# Adapter_board.net
KiCad netlist of a schematic drawn in EAGLE
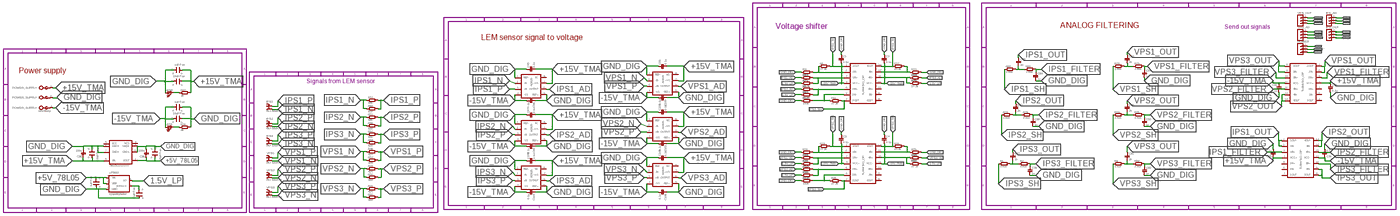
[diagram p0: schematic, sheet 1, overview]
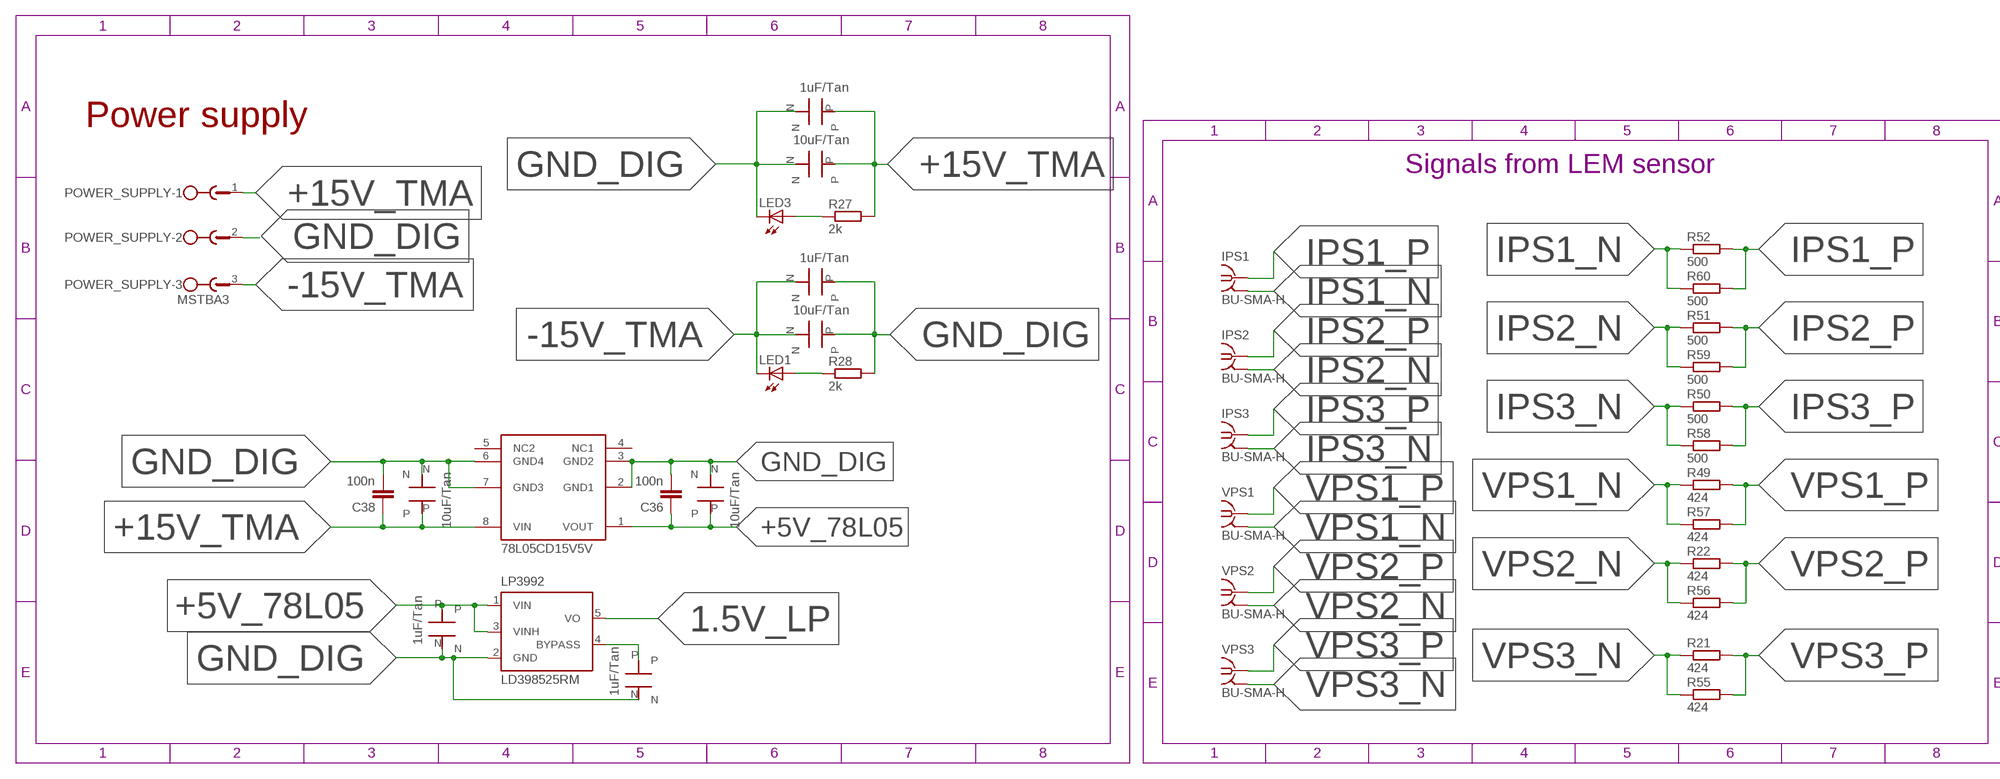
[diagram p1: schematic, sheet 1, part 1 of 4]
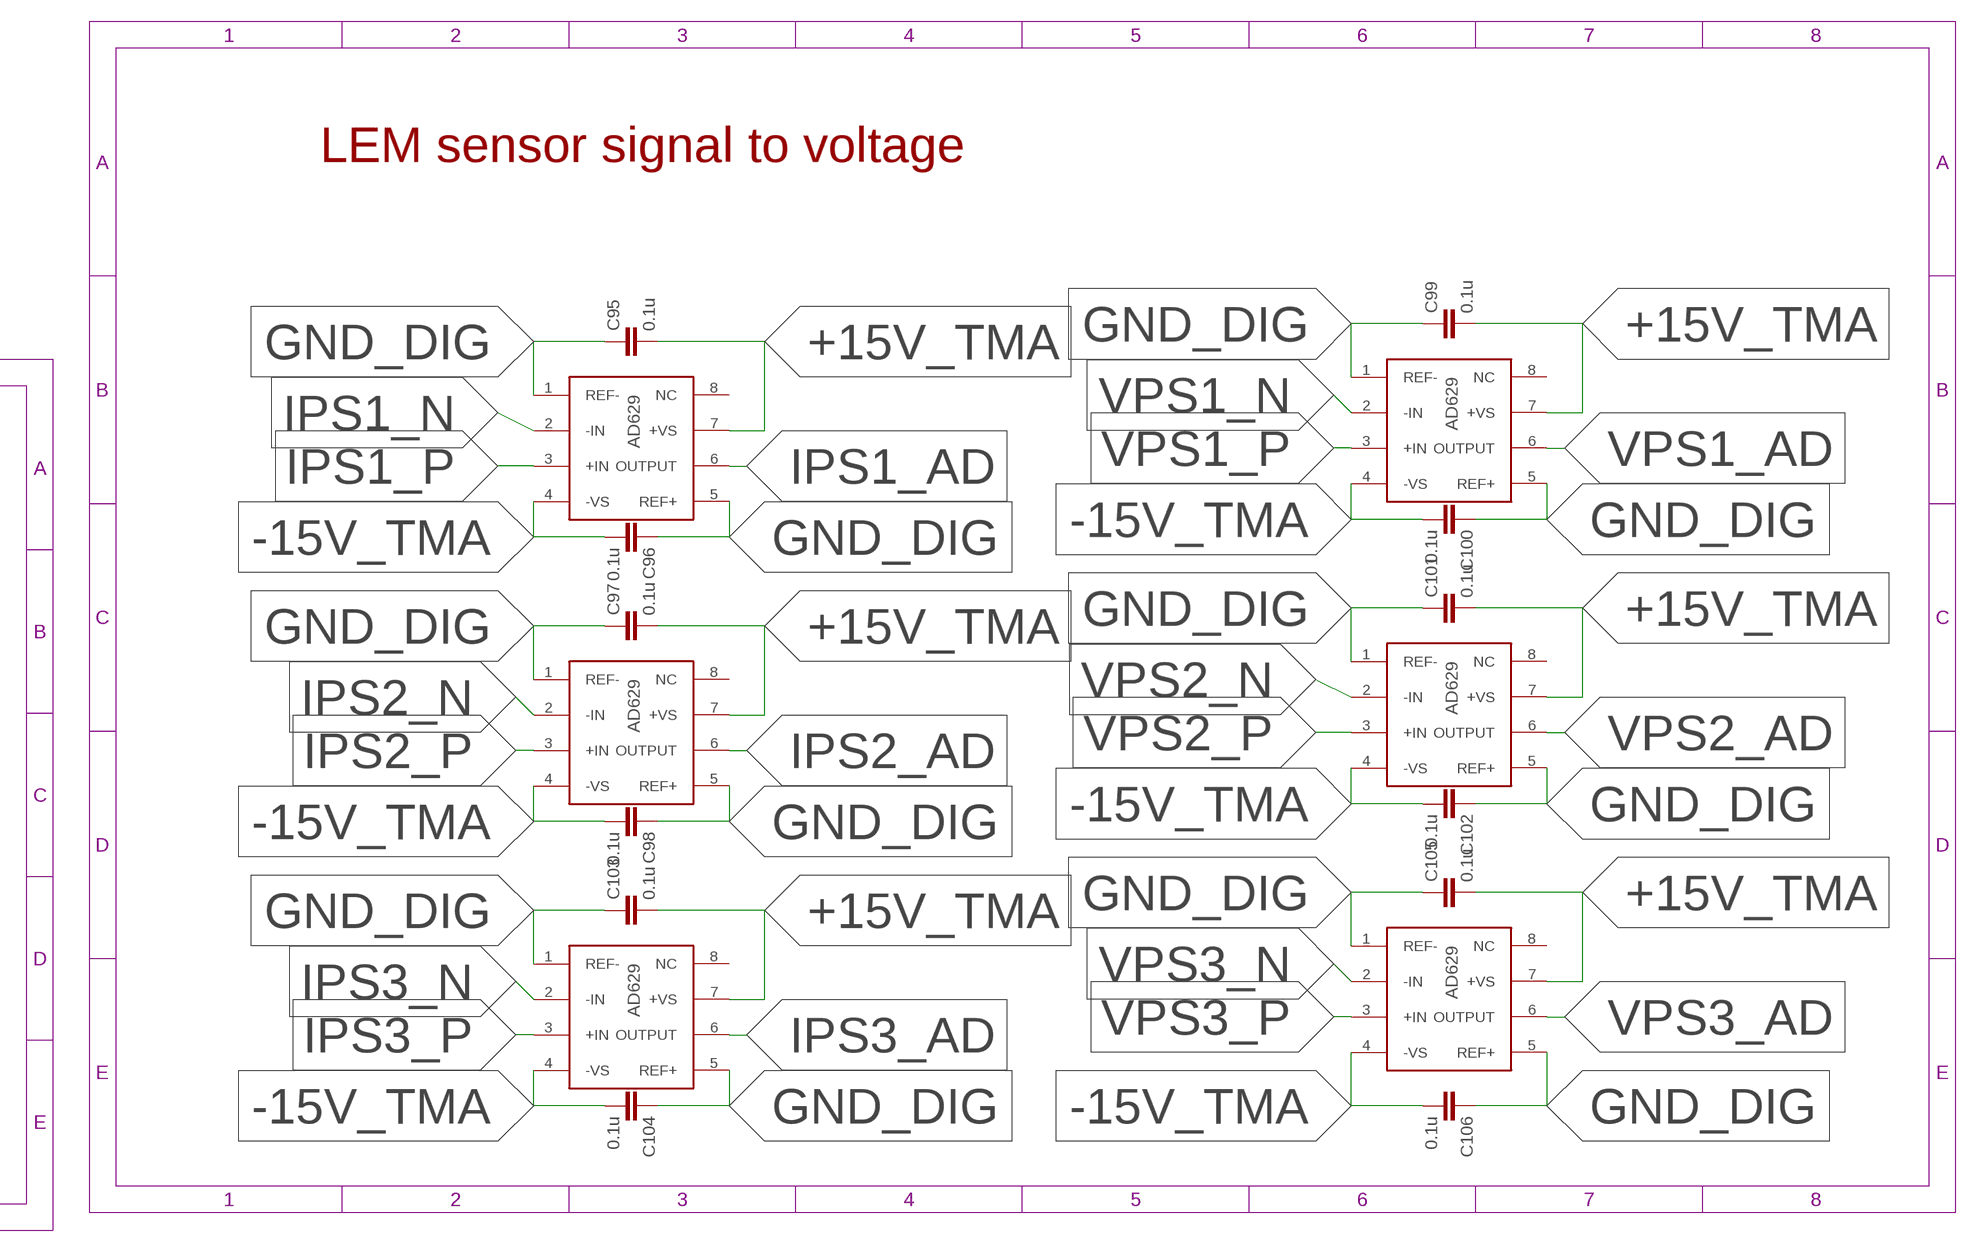
[diagram p2: schematic, sheet 1, part 2 of 4]
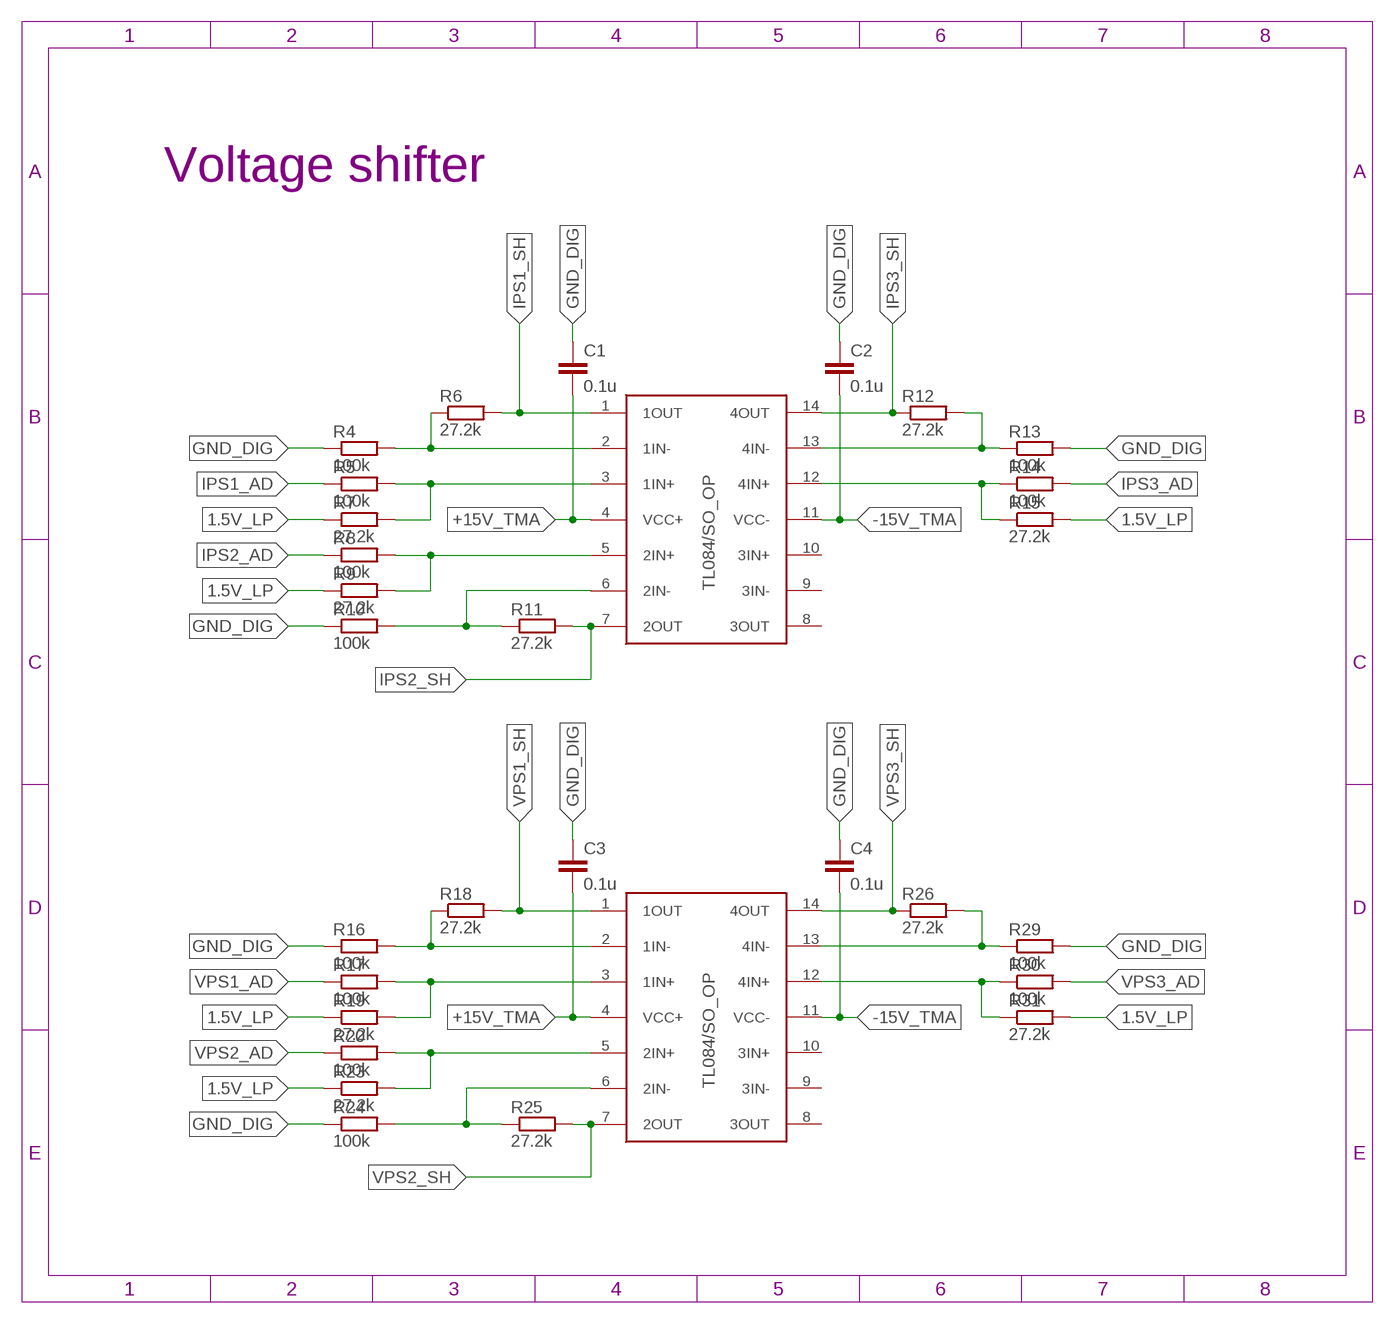
[diagram p3: schematic, sheet 1, part 3 of 4]
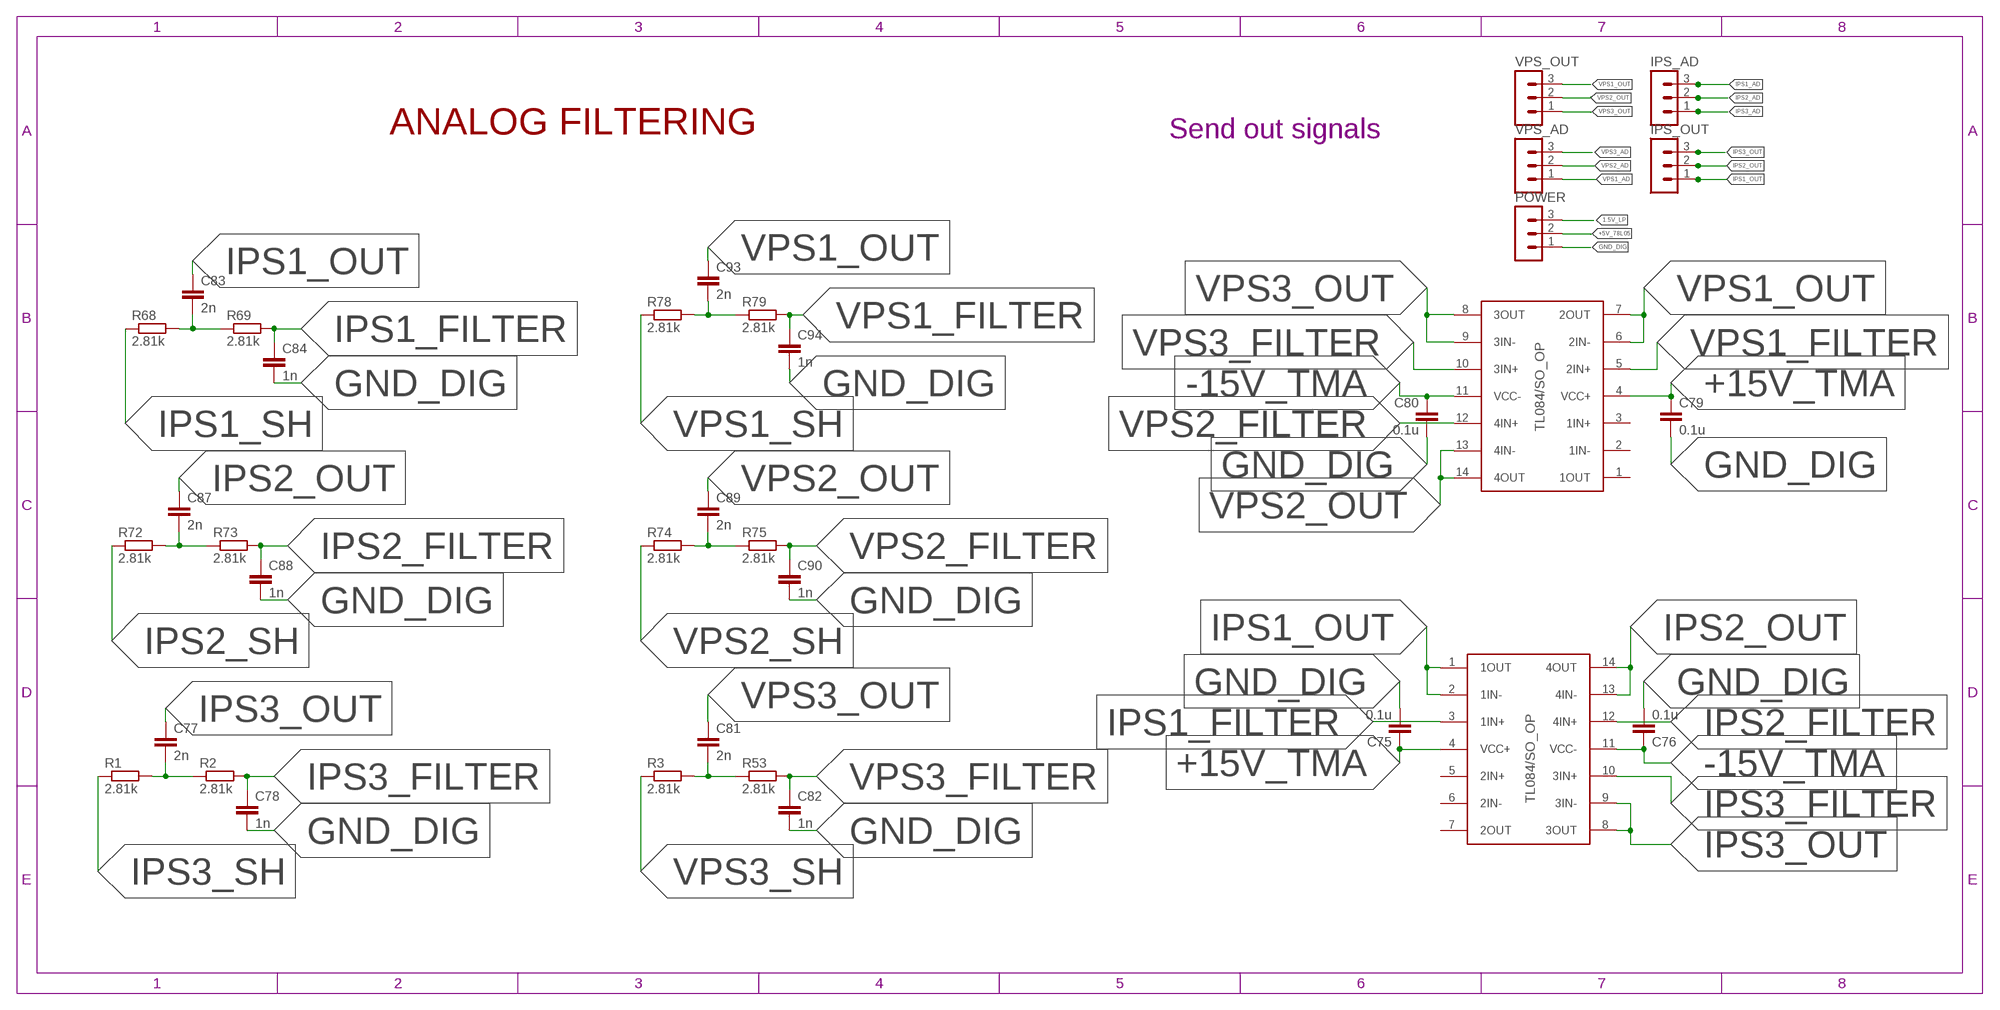
[diagram p4: schematic, sheet 1, part 4 of 4]

(export (version "E")
  (design (tool "Eeschema 10.0.6"))
  (components
    (comp (ref "78L05")
      (value "78L05CD15V5VONLINE")
      (footprint "eagle-import:78L05CD15V5V_LIB")
      (libsource (lib "eagle-import") (part "78L05CD15V5VONLINE"))
    )
    (comp (ref "C1")
      (value "0.1u")
      (footprint "eagle-import:C0805")
      (libsource (lib "eagle-import") (part "C-EUC0805"))
    )
    (comp (ref "C2")
      (value "0.1u")
      (footprint "eagle-import:C0805")
      (libsource (lib "eagle-import") (part "C-EUC0805"))
    )
    (comp (ref "C3")
      (value "0.1u")
      (footprint "eagle-import:C0805")
      (libsource (lib "eagle-import") (part "C-EUC0805"))
    )
    (comp (ref "C4")
      (value "0.1u")
      (footprint "eagle-import:C0805")
      (libsource (lib "eagle-import") (part "C-EUC0805"))
    )
    (comp (ref "C36")
      (value "100n")
      (footprint "eagle-import:C0805")
      (libsource (lib "eagle-import") (part "C-EUC0805"))
    )
    (comp (ref "C37")
      (value "TANTALUM_C_10UF_KEM")
      (footprint "eagle-import:TANTALUM_C_10UF_KEM")
      (libsource (lib "eagle-import") (part "TANTALUM_C_10UF_KEM"))
    )
    (comp (ref "C38")
      (value "100n")
      (footprint "eagle-import:C0805")
      (libsource (lib "eagle-import") (part "C-EUC0805"))
    )
    (comp (ref "C75")
      (value "0.1u")
      (footprint "eagle-import:C0805")
      (libsource (lib "eagle-import") (part "C-EUC0805"))
    )
    (comp (ref "C76")
      (value "0.1u")
      (footprint "eagle-import:C0805")
      (libsource (lib "eagle-import") (part "C-EUC0805"))
    )
    (comp (ref "C77")
      (value "2n")
      (footprint "eagle-import:C0805")
      (libsource (lib "eagle-import") (part "C-EUC0805"))
    )
    (comp (ref "C78")
      (value "1n")
      (footprint "eagle-import:C0805")
      (libsource (lib "eagle-import") (part "C-EUC0805"))
    )
    (comp (ref "C79")
      (value "0.1u")
      (footprint "eagle-import:C0805")
      (libsource (lib "eagle-import") (part "C-EUC0805"))
    )
    (comp (ref "C80")
      (value "0.1u")
      (footprint "eagle-import:C0805")
      (libsource (lib "eagle-import") (part "C-EUC0805"))
    )
    (comp (ref "C81")
      (value "2n")
      (footprint "eagle-import:C0805")
      (libsource (lib "eagle-import") (part "C-EUC0805"))
    )
    (comp (ref "C82")
      (value "1n")
      (footprint "eagle-import:C0805")
      (libsource (lib "eagle-import") (part "C-EUC0805"))
    )
    (comp (ref "C83")
      (value "2n")
      (footprint "eagle-import:C0805")
      (libsource (lib "eagle-import") (part "C-EUC0805"))
    )
    (comp (ref "C84")
      (value "1n")
      (footprint "eagle-import:C0805")
      (libsource (lib "eagle-import") (part "C-EUC0805"))
    )
    (comp (ref "C87")
      (value "2n")
      (footprint "eagle-import:C0805")
      (libsource (lib "eagle-import") (part "C-EUC0805"))
    )
    (comp (ref "C88")
      (value "1n")
      (footprint "eagle-import:C0805")
      (libsource (lib "eagle-import") (part "C-EUC0805"))
    )
    (comp (ref "C89")
      (value "2n")
      (footprint "eagle-import:C0805")
      (libsource (lib "eagle-import") (part "C-EUC0805"))
    )
    (comp (ref "C90")
      (value "1n")
      (footprint "eagle-import:C0805")
      (libsource (lib "eagle-import") (part "C-EUC0805"))
    )
    (comp (ref "C93")
      (value "2n")
      (footprint "eagle-import:C0805")
      (libsource (lib "eagle-import") (part "C-EUC0805"))
    )
    (comp (ref "C94")
      (value "1n")
      (footprint "eagle-import:C0805")
      (libsource (lib "eagle-import") (part "C-EUC0805"))
    )
    (comp (ref "C95")
      (value "0.1u")
      (footprint "eagle-import:C0805")
      (libsource (lib "eagle-import") (part "C-EUC0805"))
    )
    (comp (ref "C96")
      (value "0.1u")
      (footprint "eagle-import:C0805")
      (libsource (lib "eagle-import") (part "C-EUC0805"))
    )
    (comp (ref "C97")
      (value "0.1u")
      (footprint "eagle-import:C0805")
      (libsource (lib "eagle-import") (part "C-EUC0805"))
    )
    (comp (ref "C98")
      (value "0.1u")
      (footprint "eagle-import:C0805")
      (libsource (lib "eagle-import") (part "C-EUC0805"))
    )
    (comp (ref "C99")
      (value "0.1u")
      (footprint "eagle-import:C0805")
      (libsource (lib "eagle-import") (part "C-EUC0805"))
    )
    (comp (ref "C100")
      (value "0.1u")
      (footprint "eagle-import:C0805")
      (libsource (lib "eagle-import") (part "C-EUC0805"))
    )
    (comp (ref "C101")
      (value "0.1u")
      (footprint "eagle-import:C0805")
      (libsource (lib "eagle-import") (part "C-EUC0805"))
    )
    (comp (ref "C102")
      (value "0.1u")
      (footprint "eagle-import:C0805")
      (libsource (lib "eagle-import") (part "C-EUC0805"))
    )
    (comp (ref "C103")
      (value "0.1u")
      (footprint "eagle-import:C0805")
      (libsource (lib "eagle-import") (part "C-EUC0805"))
    )
    (comp (ref "C104")
      (value "0.1u")
      (footprint "eagle-import:C0805")
      (libsource (lib "eagle-import") (part "C-EUC0805"))
    )
    (comp (ref "C105")
      (value "0.1u")
      (footprint "eagle-import:C0805")
      (libsource (lib "eagle-import") (part "C-EUC0805"))
    )
    (comp (ref "C106")
      (value "0.1u")
      (footprint "eagle-import:C0805")
      (libsource (lib "eagle-import") (part "C-EUC0805"))
    )
    (comp (ref "IPS1")
      (value "BU-SMA-H")
      (footprint "eagle-import:BU-SMA-H")
      (libsource (lib "eagle-import") (part "BU-SMA-H"))
    )
    (comp (ref "IPS2")
      (value "BU-SMA-H")
      (footprint "eagle-import:BU-SMA-H")
      (libsource (lib "eagle-import") (part "BU-SMA-H"))
    )
    (comp (ref "IPS3")
      (value "BU-SMA-H")
      (footprint "eagle-import:BU-SMA-H")
      (libsource (lib "eagle-import") (part "BU-SMA-H"))
    )
    (comp (ref "IPS_AD")
      (value "MA03-1")
      (footprint "eagle-import:MA03-1")
      (libsource (lib "eagle-import") (part "MA03-1"))
    )
    (comp (ref "IPS_OUT")
      (value "MA03-1")
      (footprint "eagle-import:MA03-1")
      (libsource (lib "eagle-import") (part "MA03-1"))
    )
    (comp (ref "LED1")
      (value "LEDCHIPLED_0805")
      (footprint "eagle-import:CHIPLED_0805")
      (libsource (lib "eagle-import") (part "LEDCHIPLED_0805"))
    )
    (comp (ref "LED3")
      (value "LEDCHIPLED_0805")
      (footprint "eagle-import:CHIPLED_0805")
      (libsource (lib "eagle-import") (part "LEDCHIPLED_0805"))
    )
    (comp (ref "LP3992")
      (value "LD398525RM")
      (footprint "eagle-import:SOT23-5L")
      (libsource (lib "eagle-import") (part "LD3985M25R"))
    )
    (comp (ref "POWER")
      (value "MA03-1")
      (footprint "eagle-import:MA03-1")
      (libsource (lib "eagle-import") (part "MA03-1"))
    )
    (comp (ref "POWER_SUPPLY")
      (value "MSTBA3")
      (footprint "eagle-import:MSTBA3")
      (fields (field (name "MF") "FARNELL") (field (name "MPN") "1757255"))
      (libsource (lib "eagle-import") (part "MSTBA3"))
    )
    (comp (ref "R1")
      (value "2.81k")
      (footprint "eagle-import:R0805")
      (libsource (lib "eagle-import") (part "R-EU_R0805"))
    )
    (comp (ref "R2")
      (value "2.81k")
      (footprint "eagle-import:R0805")
      (libsource (lib "eagle-import") (part "R-EU_R0805"))
    )
    (comp (ref "R3")
      (value "2.81k")
      (footprint "eagle-import:R0805")
      (libsource (lib "eagle-import") (part "R-EU_R0805"))
    )
    (comp (ref "R4")
      (value "100k")
      (footprint "eagle-import:R0805")
      (libsource (lib "eagle-import") (part "R-EU_R0805"))
    )
    (comp (ref "R5")
      (value "100k")
      (footprint "eagle-import:R0805")
      (libsource (lib "eagle-import") (part "R-EU_R0805"))
    )
    (comp (ref "R6")
      (value "27.2k")
      (footprint "eagle-import:R0805")
      (libsource (lib "eagle-import") (part "R-EU_R0805"))
    )
    (comp (ref "R7")
      (value "27.2k")
      (footprint "eagle-import:R0805")
      (libsource (lib "eagle-import") (part "R-EU_R0805"))
    )
    (comp (ref "R8")
      (value "100k")
      (footprint "eagle-import:R0805")
      (libsource (lib "eagle-import") (part "R-EU_R0805"))
    )
    (comp (ref "R9")
      (value "27.2k")
      (footprint "eagle-import:R0805")
      (libsource (lib "eagle-import") (part "R-EU_R0805"))
    )
    (comp (ref "R10")
      (value "100k")
      (footprint "eagle-import:R0805")
      (libsource (lib "eagle-import") (part "R-EU_R0805"))
    )
    (comp (ref "R11")
      (value "27.2k")
      (footprint "eagle-import:R0805")
      (libsource (lib "eagle-import") (part "R-EU_R0805"))
    )
    (comp (ref "R12")
      (value "27.2k")
      (footprint "eagle-import:R0805")
      (libsource (lib "eagle-import") (part "R-EU_R0805"))
    )
    (comp (ref "R13")
      (value "100k")
      (footprint "eagle-import:R0805")
      (libsource (lib "eagle-import") (part "R-EU_R0805"))
    )
    (comp (ref "R14")
      (value "100k")
      (footprint "eagle-import:R0805")
      (libsource (lib "eagle-import") (part "R-EU_R0805"))
    )
    (comp (ref "R15")
      (value "27.2k")
      (footprint "eagle-import:R0805")
      (libsource (lib "eagle-import") (part "R-EU_R0805"))
    )
    (comp (ref "R16")
      (value "100k")
      (footprint "eagle-import:R0805")
      (libsource (lib "eagle-import") (part "R-EU_R0805"))
    )
    (comp (ref "R17")
      (value "100k")
      (footprint "eagle-import:R0805")
      (libsource (lib "eagle-import") (part "R-EU_R0805"))
    )
    (comp (ref "R18")
      (value "27.2k")
      (footprint "eagle-import:R0805")
      (libsource (lib "eagle-import") (part "R-EU_R0805"))
    )
    (comp (ref "R19")
      (value "27.2k")
      (footprint "eagle-import:R0805")
      (libsource (lib "eagle-import") (part "R-EU_R0805"))
    )
    (comp (ref "R20")
      (value "100k")
      (footprint "eagle-import:R0805")
      (libsource (lib "eagle-import") (part "R-EU_R0805"))
    )
    (comp (ref "R21")
      (value "424")
      (footprint "eagle-import:R1206")
      (libsource (lib "eagle-import") (part "R-EU_R1206"))
    )
    (comp (ref "R22")
      (value "424")
      (footprint "eagle-import:R1206")
      (libsource (lib "eagle-import") (part "R-EU_R1206"))
    )
    (comp (ref "R23")
      (value "27.2k")
      (footprint "eagle-import:R0805")
      (libsource (lib "eagle-import") (part "R-EU_R0805"))
    )
    (comp (ref "R24")
      (value "100k")
      (footprint "eagle-import:R0805")
      (libsource (lib "eagle-import") (part "R-EU_R0805"))
    )
    (comp (ref "R25")
      (value "27.2k")
      (footprint "eagle-import:R0805")
      (libsource (lib "eagle-import") (part "R-EU_R0805"))
    )
    (comp (ref "R26")
      (value "27.2k")
      (footprint "eagle-import:R0805")
      (libsource (lib "eagle-import") (part "R-EU_R0805"))
    )
    (comp (ref "R27")
      (value "2k")
      (footprint "eagle-import:R0805")
      (libsource (lib "eagle-import") (part "R-EU_R0805"))
    )
    (comp (ref "R28")
      (value "2k")
      (footprint "eagle-import:R0805")
      (libsource (lib "eagle-import") (part "R-EU_R0805"))
    )
    (comp (ref "R29")
      (value "100k")
      (footprint "eagle-import:R0805")
      (libsource (lib "eagle-import") (part "R-EU_R0805"))
    )
    (comp (ref "R30")
      (value "100k")
      (footprint "eagle-import:R0805")
      (libsource (lib "eagle-import") (part "R-EU_R0805"))
    )
    (comp (ref "R31")
      (value "27.2k")
      (footprint "eagle-import:R0805")
      (libsource (lib "eagle-import") (part "R-EU_R0805"))
    )
    (comp (ref "R49")
      (value "424")
      (footprint "eagle-import:R1206")
      (libsource (lib "eagle-import") (part "R-EU_R1206"))
    )
    (comp (ref "R50")
      (value "500")
      (footprint "eagle-import:R1206")
      (libsource (lib "eagle-import") (part "R-EU_R1206"))
    )
    (comp (ref "R51")
      (value "500")
      (footprint "eagle-import:R1206")
      (libsource (lib "eagle-import") (part "R-EU_R1206"))
    )
    (comp (ref "R52")
      (value "500")
      (footprint "eagle-import:R1206")
      (libsource (lib "eagle-import") (part "R-EU_R1206"))
    )
    (comp (ref "R53")
      (value "2.81k")
      (footprint "eagle-import:R0805")
      (libsource (lib "eagle-import") (part "R-EU_R0805"))
    )
    (comp (ref "R55")
      (value "424")
      (footprint "eagle-import:R1206")
      (libsource (lib "eagle-import") (part "R-EU_R1206"))
    )
    (comp (ref "R56")
      (value "424")
      (footprint "eagle-import:R1206")
      (libsource (lib "eagle-import") (part "R-EU_R1206"))
    )
    (comp (ref "R57")
      (value "424")
      (footprint "eagle-import:R1206")
      (libsource (lib "eagle-import") (part "R-EU_R1206"))
    )
    (comp (ref "R58")
      (value "500")
      (footprint "eagle-import:R1206")
      (libsource (lib "eagle-import") (part "R-EU_R1206"))
    )
    (comp (ref "R59")
      (value "500")
      (footprint "eagle-import:R1206")
      (libsource (lib "eagle-import") (part "R-EU_R1206"))
    )
    (comp (ref "R60")
      (value "500")
      (footprint "eagle-import:R1206")
      (libsource (lib "eagle-import") (part "R-EU_R1206"))
    )
    (comp (ref "R68")
      (value "2.81k")
      (footprint "eagle-import:R0805")
      (libsource (lib "eagle-import") (part "R-EU_R0805"))
    )
    (comp (ref "R69")
      (value "2.81k")
      (footprint "eagle-import:R0805")
      (libsource (lib "eagle-import") (part "R-EU_R0805"))
    )
    (comp (ref "R72")
      (value "2.81k")
      (footprint "eagle-import:R0805")
      (libsource (lib "eagle-import") (part "R-EU_R0805"))
    )
    (comp (ref "R73")
      (value "2.81k")
      (footprint "eagle-import:R0805")
      (libsource (lib "eagle-import") (part "R-EU_R0805"))
    )
    (comp (ref "R74")
      (value "2.81k")
      (footprint "eagle-import:R0805")
      (libsource (lib "eagle-import") (part "R-EU_R0805"))
    )
    (comp (ref "R75")
      (value "2.81k")
      (footprint "eagle-import:R0805")
      (libsource (lib "eagle-import") (part "R-EU_R0805"))
    )
    (comp (ref "R78")
      (value "2.81k")
      (footprint "eagle-import:R0805")
      (libsource (lib "eagle-import") (part "R-EU_R0805"))
    )
    (comp (ref "R79")
      (value "2.81k")
      (footprint "eagle-import:R0805")
      (libsource (lib "eagle-import") (part "R-EU_R0805"))
    )
    (comp (ref "U$1")
      (value "TL084/SO_OPONLINE")
      (footprint "eagle-import:TL084_SO_OP_LIB")
      (libsource (lib "eagle-import") (part "TL084/SO_OPONLINE"))
    )
    (comp (ref "U$2")
      (value "TL084/SO_OPONLINE")
      (footprint "eagle-import:TL084_SO_OP_LIB")
      (libsource (lib "eagle-import") (part "TL084/SO_OPONLINE"))
    )
    (comp (ref "U$3")
      (value "TANTALUM_C_1UF_KEMTANTALUM_C_1UF_KEM")
      (footprint "eagle-import:TANTALUM_C_1UF_KEM")
      (libsource (lib "eagle-import") (part "TANTALUM_C_1UF_KEMTANTALUM_C_1UF_KEM"))
    )
    (comp (ref "U$4")
      (value "TL084/SO_OPONLINE")
      (footprint "eagle-import:TL084_SO_OP_LIB")
      (libsource (lib "eagle-import") (part "TL084/SO_OPONLINE"))
    )
    (comp (ref "U$5")
      (value "TANTALUM_C_1UF_KEMTANTALUM_C_1UF_KEM")
      (footprint "eagle-import:TANTALUM_C_1UF_KEM")
      (libsource (lib "eagle-import") (part "TANTALUM_C_1UF_KEMTANTALUM_C_1UF_KEM"))
    )
    (comp (ref "U$6")
      (value "TL084/SO_OPONLINE")
      (footprint "eagle-import:TL084_SO_OP_LIB")
      (libsource (lib "eagle-import") (part "TL084/SO_OPONLINE"))
    )
    (comp (ref "U$10")
      (value "TANTALUM_C_1UF_KEMTANTALUM_C_1UF_KEM")
      (footprint "eagle-import:TANTALUM_C_1UF_KEM")
      (libsource (lib "eagle-import") (part "TANTALUM_C_1UF_KEMTANTALUM_C_1UF_KEM"))
    )
    (comp (ref "U$11")
      (value "TANTALUM_C_10UF_KEM")
      (footprint "eagle-import:TANTALUM_C_10UF_KEM")
      (libsource (lib "eagle-import") (part "TANTALUM_C_10UF_KEM"))
    )
    (comp (ref "U$12")
      (value "TANTALUM_C_1UF_KEMTANTALUM_C_1UF_KEM")
      (footprint "eagle-import:TANTALUM_C_1UF_KEM")
      (libsource (lib "eagle-import") (part "TANTALUM_C_1UF_KEMTANTALUM_C_1UF_KEM"))
    )
    (comp (ref "U$14")
      (value "TANTALUM_C_10UF_KEM")
      (footprint "eagle-import:TANTALUM_C_10UF_KEM")
      (libsource (lib "eagle-import") (part "TANTALUM_C_10UF_KEM"))
    )
    (comp (ref "U$24")
      (value "AD629_DIFFAONLINE")
      (footprint "eagle-import:AD629_DIFFA_LIB")
      (libsource (lib "eagle-import") (part "AD629_DIFFAONLINE"))
    )
    (comp (ref "U$27")
      (value "AD629_DIFFAONLINE")
      (footprint "eagle-import:AD629_DIFFA_LIB")
      (libsource (lib "eagle-import") (part "AD629_DIFFAONLINE"))
    )
    (comp (ref "U$28")
      (value "AD629_DIFFAONLINE")
      (footprint "eagle-import:AD629_DIFFA_LIB")
      (libsource (lib "eagle-import") (part "AD629_DIFFAONLINE"))
    )
    (comp (ref "U$29")
      (value "AD629_DIFFAONLINE")
      (footprint "eagle-import:AD629_DIFFA_LIB")
      (libsource (lib "eagle-import") (part "AD629_DIFFAONLINE"))
    )
    (comp (ref "U$30")
      (value "AD629_DIFFAONLINE")
      (footprint "eagle-import:AD629_DIFFA_LIB")
      (libsource (lib "eagle-import") (part "AD629_DIFFAONLINE"))
    )
    (comp (ref "U$31")
      (value "AD629_DIFFAONLINE")
      (footprint "eagle-import:AD629_DIFFA_LIB")
      (libsource (lib "eagle-import") (part "AD629_DIFFAONLINE"))
    )
    (comp (ref "U$66")
      (value "TANTALUM_C_10UF_KEM")
      (footprint "eagle-import:TANTALUM_C_10UF_KEM")
      (libsource (lib "eagle-import") (part "TANTALUM_C_10UF_KEM"))
    )
    (comp (ref "VPS1")
      (value "BU-SMA-H")
      (footprint "eagle-import:BU-SMA-H")
      (libsource (lib "eagle-import") (part "BU-SMA-H"))
    )
    (comp (ref "VPS2")
      (value "BU-SMA-H")
      (footprint "eagle-import:BU-SMA-H")
      (libsource (lib "eagle-import") (part "BU-SMA-H"))
    )
    (comp (ref "VPS3")
      (value "BU-SMA-H")
      (footprint "eagle-import:BU-SMA-H")
      (libsource (lib "eagle-import") (part "BU-SMA-H"))
    )
    (comp (ref "VPS_AD")
      (value "MA03-1")
      (footprint "eagle-import:MA03-1")
      (libsource (lib "eagle-import") (part "MA03-1"))
    )
    (comp (ref "VPS_OUT")
      (value "MA03-1")
      (footprint "eagle-import:MA03-1")
      (libsource (lib "eagle-import") (part "MA03-1"))
    )
  )
  (nets
    (net (code "1") (name "+5V_78L05") (class "Default")
      (node (ref "78L05") (pin "1") (pinfunction "VOUT_1") (pintype "bidirectional"))
      (node (ref "C36") (pin "1") (pinfunction "1_1") (pintype "passive"))
      (node (ref "C37") (pin "P") (pinfunction "P_P") (pintype "bidirectional"))
      (node (ref "LP3992") (pin "1") (pinfunction "VIN_1") (pintype "input"))
      (node (ref "LP3992") (pin "3") (pinfunction "VINH_3") (pintype "input"))
      (node (ref "POWER") (pin "2") (pinfunction "2_2") (pintype "passive"))
      (node (ref "U$3") (pin "P") (pinfunction "P_P") (pintype "bidirectional"))
    )
    (net (code "2") (name "+15V_TMA") (class "Default")
      (node (ref "78L05") (pin "8") (pinfunction "VIN_8") (pintype "bidirectional"))
      (node (ref "C1") (pin "2") (pinfunction "2_2") (pintype "passive"))
      (node (ref "C101") (pin "2") (pinfunction "2_2") (pintype "passive"))
      (node (ref "C103") (pin "2") (pinfunction "2_2") (pintype "passive"))
      (node (ref "C105") (pin "2") (pinfunction "2_2") (pintype "passive"))
      (node (ref "C3") (pin "2") (pinfunction "2_2") (pintype "passive"))
      (node (ref "C38") (pin "1") (pinfunction "1_1") (pintype "passive"))
      (node (ref "C75") (pin "1") (pinfunction "1_1") (pintype "passive"))
      (node (ref "C79") (pin "1") (pinfunction "1_1") (pintype "passive"))
      (node (ref "C95") (pin "2") (pinfunction "2_2") (pintype "passive"))
      (node (ref "C97") (pin "2") (pinfunction "2_2") (pintype "passive"))
      (node (ref "C99") (pin "2") (pinfunction "2_2") (pintype "passive"))
      (node (ref "POWER_SUPPLY") (pin "1") (pinfunction "1_1") (pintype "passive"))
      (node (ref "R27") (pin "2") (pinfunction "2_2") (pintype "passive"))
      (node (ref "U$1") (pin "4") (pinfunction "VCC+_4") (pintype "bidirectional"))
      (node (ref "U$10") (pin "P") (pinfunction "P_P") (pintype "bidirectional"))
      (node (ref "U$11") (pin "P") (pinfunction "P_P") (pintype "bidirectional"))
      (node (ref "U$2") (pin "4") (pinfunction "VCC+_4") (pintype "bidirectional"))
      (node (ref "U$24") (pin "7") (pinfunction "+VS_7") (pintype "bidirectional"))
      (node (ref "U$27") (pin "7") (pinfunction "+VS_7") (pintype "bidirectional"))
      (node (ref "U$28") (pin "7") (pinfunction "+VS_7") (pintype "bidirectional"))
      (node (ref "U$29") (pin "7") (pinfunction "+VS_7") (pintype "bidirectional"))
      (node (ref "U$30") (pin "7") (pinfunction "+VS_7") (pintype "bidirectional"))
      (node (ref "U$31") (pin "7") (pinfunction "+VS_7") (pintype "bidirectional"))
      (node (ref "U$4") (pin "4") (pinfunction "VCC+_4") (pintype "bidirectional"))
      (node (ref "U$6") (pin "4") (pinfunction "VCC+_4") (pintype "bidirectional"))
      (node (ref "U$66") (pin "P") (pinfunction "P_P") (pintype "bidirectional"))
    )
    (net (code "3") (name "-15V_TMA") (class "Default")
      (node (ref "C100") (pin "2") (pinfunction "2_2") (pintype "passive"))
      (node (ref "C102") (pin "2") (pinfunction "2_2") (pintype "passive"))
      (node (ref "C104") (pin "2") (pinfunction "2_2") (pintype "passive"))
      (node (ref "C106") (pin "2") (pinfunction "2_2") (pintype "passive"))
      (node (ref "C2") (pin "2") (pinfunction "2_2") (pintype "passive"))
      (node (ref "C4") (pin "2") (pinfunction "2_2") (pintype "passive"))
      (node (ref "C76") (pin "1") (pinfunction "1_1") (pintype "passive"))
      (node (ref "C80") (pin "1") (pinfunction "1_1") (pintype "passive"))
      (node (ref "C96") (pin "2") (pinfunction "2_2") (pintype "passive"))
      (node (ref "C98") (pin "2") (pinfunction "2_2") (pintype "passive"))
      (node (ref "LED1") (pin "C") (pinfunction "C_C") (pintype "passive"))
      (node (ref "POWER_SUPPLY") (pin "3") (pinfunction "1_3") (pintype "passive"))
      (node (ref "U$1") (pin "11") (pinfunction "VCC-_11") (pintype "bidirectional"))
      (node (ref "U$12") (pin "N") (pinfunction "N_N") (pintype "bidirectional"))
      (node (ref "U$14") (pin "N") (pinfunction "N_N") (pintype "bidirectional"))
      (node (ref "U$2") (pin "11") (pinfunction "VCC-_11") (pintype "bidirectional"))
      (node (ref "U$24") (pin "4") (pinfunction "-VS_4") (pintype "bidirectional"))
      (node (ref "U$27") (pin "4") (pinfunction "-VS_4") (pintype "bidirectional"))
      (node (ref "U$28") (pin "4") (pinfunction "-VS_4") (pintype "bidirectional"))
      (node (ref "U$29") (pin "4") (pinfunction "-VS_4") (pintype "bidirectional"))
      (node (ref "U$30") (pin "4") (pinfunction "-VS_4") (pintype "bidirectional"))
      (node (ref "U$31") (pin "4") (pinfunction "-VS_4") (pintype "bidirectional"))
      (node (ref "U$4") (pin "11") (pinfunction "VCC-_11") (pintype "bidirectional"))
      (node (ref "U$6") (pin "11") (pinfunction "VCC-_11") (pintype "bidirectional"))
    )
    (net (code "4") (name "1.5V_LP") (class "Default")
      (node (ref "LP3992") (pin "5") (pinfunction "VO_5") (pintype "output"))
      (node (ref "POWER") (pin "3") (pinfunction "3_3") (pintype "passive"))
      (node (ref "R15") (pin "2") (pinfunction "2_2") (pintype "passive"))
      (node (ref "R19") (pin "1") (pinfunction "1_1") (pintype "passive"))
      (node (ref "R23") (pin "1") (pinfunction "1_1") (pintype "passive"))
      (node (ref "R31") (pin "2") (pinfunction "2_2") (pintype "passive"))
      (node (ref "R7") (pin "1") (pinfunction "1_1") (pintype "passive"))
      (node (ref "R9") (pin "1") (pinfunction "1_1") (pintype "passive"))
    )
    (net (code "5") (name "GND_DIG") (class "Default")
      (node (ref "78L05") (pin "2") (pinfunction "GND1_2") (pintype "bidirectional"))
      (node (ref "78L05") (pin "3") (pinfunction "GND2_3") (pintype "bidirectional"))
      (node (ref "78L05") (pin "6") (pinfunction "GND4_6") (pintype "bidirectional"))
      (node (ref "78L05") (pin "7") (pinfunction "GND3_7") (pintype "bidirectional"))
      (node (ref "C1") (pin "1") (pinfunction "1_1") (pintype "passive"))
      (node (ref "C100") (pin "1") (pinfunction "1_1") (pintype "passive"))
      (node (ref "C101") (pin "1") (pinfunction "1_1") (pintype "passive"))
      (node (ref "C102") (pin "1") (pinfunction "1_1") (pintype "passive"))
      (node (ref "C103") (pin "1") (pinfunction "1_1") (pintype "passive"))
      (node (ref "C104") (pin "1") (pinfunction "1_1") (pintype "passive"))
      (node (ref "C105") (pin "1") (pinfunction "1_1") (pintype "passive"))
      (node (ref "C106") (pin "1") (pinfunction "1_1") (pintype "passive"))
      (node (ref "C2") (pin "1") (pinfunction "1_1") (pintype "passive"))
      (node (ref "C3") (pin "1") (pinfunction "1_1") (pintype "passive"))
      (node (ref "C36") (pin "2") (pinfunction "2_2") (pintype "passive"))
      (node (ref "C37") (pin "N") (pinfunction "N_N") (pintype "bidirectional"))
      (node (ref "C38") (pin "2") (pinfunction "2_2") (pintype "passive"))
      (node (ref "C4") (pin "1") (pinfunction "1_1") (pintype "passive"))
      (node (ref "C75") (pin "2") (pinfunction "2_2") (pintype "passive"))
      (node (ref "C76") (pin "2") (pinfunction "2_2") (pintype "passive"))
      (node (ref "C78") (pin "2") (pinfunction "2_2") (pintype "passive"))
      (node (ref "C79") (pin "2") (pinfunction "2_2") (pintype "passive"))
      (node (ref "C80") (pin "2") (pinfunction "2_2") (pintype "passive"))
      (node (ref "C82") (pin "2") (pinfunction "2_2") (pintype "passive"))
      (node (ref "C84") (pin "2") (pinfunction "2_2") (pintype "passive"))
      (node (ref "C88") (pin "2") (pinfunction "2_2") (pintype "passive"))
      (node (ref "C90") (pin "2") (pinfunction "2_2") (pintype "passive"))
      (node (ref "C94") (pin "2") (pinfunction "2_2") (pintype "passive"))
      (node (ref "C95") (pin "1") (pinfunction "1_1") (pintype "passive"))
      (node (ref "C96") (pin "1") (pinfunction "1_1") (pintype "passive"))
      (node (ref "C97") (pin "1") (pinfunction "1_1") (pintype "passive"))
      (node (ref "C98") (pin "1") (pinfunction "1_1") (pintype "passive"))
      (node (ref "C99") (pin "1") (pinfunction "1_1") (pintype "passive"))
      (node (ref "LED3") (pin "C") (pinfunction "C_C") (pintype "passive"))
      (node (ref "LP3992") (pin "2") (pinfunction "GND_2") (pintype "power_in"))
      (node (ref "POWER") (pin "1") (pinfunction "1_1") (pintype "passive"))
      (node (ref "POWER_SUPPLY") (pin "2") (pinfunction "1_2") (pintype "passive"))
      (node (ref "R10") (pin "1") (pinfunction "1_1") (pintype "passive"))
      (node (ref "R13") (pin "2") (pinfunction "2_2") (pintype "passive"))
      (node (ref "R16") (pin "1") (pinfunction "1_1") (pintype "passive"))
      (node (ref "R24") (pin "1") (pinfunction "1_1") (pintype "passive"))
      (node (ref "R28") (pin "2") (pinfunction "2_2") (pintype "passive"))
      (node (ref "R29") (pin "2") (pinfunction "2_2") (pintype "passive"))
      (node (ref "R4") (pin "1") (pinfunction "1_1") (pintype "passive"))
      (node (ref "U$10") (pin "N") (pinfunction "N_N") (pintype "bidirectional"))
      (node (ref "U$11") (pin "N") (pinfunction "N_N") (pintype "bidirectional"))
      (node (ref "U$12") (pin "P") (pinfunction "P_P") (pintype "bidirectional"))
      (node (ref "U$14") (pin "P") (pinfunction "P_P") (pintype "bidirectional"))
      (node (ref "U$24") (pin "1") (pinfunction "REF-_1") (pintype "bidirectional"))
      (node (ref "U$24") (pin "5") (pinfunction "REF+_5") (pintype "bidirectional"))
      (node (ref "U$27") (pin "1") (pinfunction "REF-_1") (pintype "bidirectional"))
      (node (ref "U$27") (pin "5") (pinfunction "REF+_5") (pintype "bidirectional"))
      (node (ref "U$28") (pin "1") (pinfunction "REF-_1") (pintype "bidirectional"))
      (node (ref "U$28") (pin "5") (pinfunction "REF+_5") (pintype "bidirectional"))
      (node (ref "U$29") (pin "1") (pinfunction "REF-_1") (pintype "bidirectional"))
      (node (ref "U$29") (pin "5") (pinfunction "REF+_5") (pintype "bidirectional"))
      (node (ref "U$3") (pin "N") (pinfunction "N_N") (pintype "bidirectional"))
      (node (ref "U$30") (pin "1") (pinfunction "REF-_1") (pintype "bidirectional"))
      (node (ref "U$30") (pin "5") (pinfunction "REF+_5") (pintype "bidirectional"))
      (node (ref "U$31") (pin "1") (pinfunction "REF-_1") (pintype "bidirectional"))
      (node (ref "U$31") (pin "5") (pinfunction "REF+_5") (pintype "bidirectional"))
      (node (ref "U$5") (pin "N") (pinfunction "N_N") (pintype "bidirectional"))
      (node (ref "U$66") (pin "N") (pinfunction "N_N") (pintype "bidirectional"))
    )
    (net (code "6") (name "IPS1_AD") (class "Default")
      (node (ref "IPS_AD") (pin "3") (pinfunction "3_3") (pintype "passive"))
      (node (ref "R5") (pin "1") (pinfunction "1_1") (pintype "passive"))
      (node (ref "U$24") (pin "6") (pinfunction "OUTPUT_6") (pintype "bidirectional"))
    )
    (net (code "7") (name "IPS1_FILTER") (class "Default")
      (node (ref "C84") (pin "1") (pinfunction "1_1") (pintype "passive"))
      (node (ref "R69") (pin "2") (pinfunction "2_2") (pintype "passive"))
      (node (ref "U$4") (pin "3") (pinfunction "1IN+_3") (pintype "bidirectional"))
    )
    (net (code "8") (name "IPS1_N") (class "Default")
      (node (ref "IPS1") (pin "2") (pinfunction "2_2") (pintype "passive"))
      (node (ref "IPS1") (pin "3") (pinfunction "2_3") (pintype "passive"))
      (node (ref "IPS1") (pin "4") (pinfunction "2_4") (pintype "passive"))
      (node (ref "IPS1") (pin "5") (pinfunction "2_5") (pintype "passive"))
      (node (ref "R52") (pin "1") (pinfunction "1_1") (pintype "passive"))
      (node (ref "R60") (pin "1") (pinfunction "1_1") (pintype "passive"))
      (node (ref "U$24") (pin "2") (pinfunction "-IN_2") (pintype "bidirectional"))
    )
    (net (code "9") (name "IPS1_OUT") (class "Default")
      (node (ref "C83") (pin "1") (pinfunction "1_1") (pintype "passive"))
      (node (ref "IPS_OUT") (pin "1") (pinfunction "1_1") (pintype "passive"))
      (node (ref "U$4") (pin "1") (pinfunction "1OUT_1") (pintype "bidirectional"))
      (node (ref "U$4") (pin "2") (pinfunction "1IN-_2") (pintype "bidirectional"))
    )
    (net (code "10") (name "IPS1_P") (class "Default")
      (node (ref "IPS1") (pin "1") (pinfunction "1_1") (pintype "passive"))
      (node (ref "R52") (pin "2") (pinfunction "2_2") (pintype "passive"))
      (node (ref "R60") (pin "2") (pinfunction "2_2") (pintype "passive"))
      (node (ref "U$24") (pin "3") (pinfunction "+IN_3") (pintype "bidirectional"))
    )
    (net (code "11") (name "IPS1_SH") (class "Default")
      (node (ref "R6") (pin "2") (pinfunction "2_2") (pintype "passive"))
      (node (ref "R68") (pin "1") (pinfunction "1_1") (pintype "passive"))
      (node (ref "U$1") (pin "1") (pinfunction "1OUT_1") (pintype "bidirectional"))
    )
    (net (code "12") (name "IPS2_AD") (class "Default")
      (node (ref "IPS_AD") (pin "2") (pinfunction "2_2") (pintype "passive"))
      (node (ref "R8") (pin "1") (pinfunction "1_1") (pintype "passive"))
      (node (ref "U$27") (pin "6") (pinfunction "OUTPUT_6") (pintype "bidirectional"))
    )
    (net (code "13") (name "IPS2_FILTER") (class "Default")
      (node (ref "C88") (pin "1") (pinfunction "1_1") (pintype "passive"))
      (node (ref "R73") (pin "2") (pinfunction "2_2") (pintype "passive"))
      (node (ref "U$4") (pin "12") (pinfunction "4IN+_12") (pintype "bidirectional"))
    )
    (net (code "14") (name "IPS2_N") (class "Default")
      (node (ref "IPS2") (pin "2") (pinfunction "2_2") (pintype "passive"))
      (node (ref "IPS2") (pin "3") (pinfunction "2_3") (pintype "passive"))
      (node (ref "IPS2") (pin "4") (pinfunction "2_4") (pintype "passive"))
      (node (ref "IPS2") (pin "5") (pinfunction "2_5") (pintype "passive"))
      (node (ref "R51") (pin "1") (pinfunction "1_1") (pintype "passive"))
      (node (ref "R59") (pin "1") (pinfunction "1_1") (pintype "passive"))
      (node (ref "U$27") (pin "2") (pinfunction "-IN_2") (pintype "bidirectional"))
    )
    (net (code "15") (name "IPS2_OUT") (class "Default")
      (node (ref "C87") (pin "1") (pinfunction "1_1") (pintype "passive"))
      (node (ref "IPS_OUT") (pin "2") (pinfunction "2_2") (pintype "passive"))
      (node (ref "U$4") (pin "13") (pinfunction "4IN-_13") (pintype "bidirectional"))
      (node (ref "U$4") (pin "14") (pinfunction "4OUT_14") (pintype "bidirectional"))
    )
    (net (code "16") (name "IPS2_P") (class "Default")
      (node (ref "IPS2") (pin "1") (pinfunction "1_1") (pintype "passive"))
      (node (ref "R51") (pin "2") (pinfunction "2_2") (pintype "passive"))
      (node (ref "R59") (pin "2") (pinfunction "2_2") (pintype "passive"))
      (node (ref "U$27") (pin "3") (pinfunction "+IN_3") (pintype "bidirectional"))
    )
    (net (code "17") (name "IPS2_SH") (class "Default")
      (node (ref "R11") (pin "2") (pinfunction "2_2") (pintype "passive"))
      (node (ref "R72") (pin "1") (pinfunction "1_1") (pintype "passive"))
      (node (ref "U$1") (pin "7") (pinfunction "2OUT_7") (pintype "bidirectional"))
    )
    (net (code "18") (name "IPS3_AD") (class "Default")
      (node (ref "IPS_AD") (pin "1") (pinfunction "1_1") (pintype "passive"))
      (node (ref "R14") (pin "2") (pinfunction "2_2") (pintype "passive"))
      (node (ref "U$30") (pin "6") (pinfunction "OUTPUT_6") (pintype "bidirectional"))
    )
    (net (code "19") (name "IPS3_FILTER") (class "Default")
      (node (ref "C78") (pin "1") (pinfunction "1_1") (pintype "passive"))
      (node (ref "R2") (pin "2") (pinfunction "2_2") (pintype "passive"))
      (node (ref "U$4") (pin "10") (pinfunction "3IN+_10") (pintype "bidirectional"))
    )
    (net (code "20") (name "IPS3_N") (class "Default")
      (node (ref "IPS3") (pin "2") (pinfunction "2_2") (pintype "passive"))
      (node (ref "IPS3") (pin "3") (pinfunction "2_3") (pintype "passive"))
      (node (ref "IPS3") (pin "4") (pinfunction "2_4") (pintype "passive"))
      (node (ref "IPS3") (pin "5") (pinfunction "2_5") (pintype "passive"))
      (node (ref "R50") (pin "1") (pinfunction "1_1") (pintype "passive"))
      (node (ref "R58") (pin "1") (pinfunction "1_1") (pintype "passive"))
      (node (ref "U$30") (pin "2") (pinfunction "-IN_2") (pintype "bidirectional"))
    )
    (net (code "21") (name "IPS3_OUT") (class "Default")
      (node (ref "C77") (pin "1") (pinfunction "1_1") (pintype "passive"))
      (node (ref "IPS_OUT") (pin "3") (pinfunction "3_3") (pintype "passive"))
      (node (ref "U$4") (pin "8") (pinfunction "3OUT_8") (pintype "bidirectional"))
      (node (ref "U$4") (pin "9") (pinfunction "3IN-_9") (pintype "bidirectional"))
    )
    (net (code "22") (name "IPS3_P") (class "Default")
      (node (ref "IPS3") (pin "1") (pinfunction "1_1") (pintype "passive"))
      (node (ref "R50") (pin "2") (pinfunction "2_2") (pintype "passive"))
      (node (ref "R58") (pin "2") (pinfunction "2_2") (pintype "passive"))
      (node (ref "U$30") (pin "3") (pinfunction "+IN_3") (pintype "bidirectional"))
    )
    (net (code "23") (name "IPS3_SH") (class "Default")
      (node (ref "R1") (pin "1") (pinfunction "1_1") (pintype "passive"))
      (node (ref "R12") (pin "1") (pinfunction "1_1") (pintype "passive"))
      (node (ref "U$1") (pin "14") (pinfunction "4OUT_14") (pintype "bidirectional"))
    )
    (net (code "24") (name "Net-(C77-Pad2)") (class "Default")
      (node (ref "C77") (pin "2") (pinfunction "2_2") (pintype "passive"))
      (node (ref "R1") (pin "2") (pinfunction "2_2") (pintype "passive"))
      (node (ref "R2") (pin "1") (pinfunction "1_1") (pintype "passive"))
    )
    (net (code "25") (name "Net-(C81-Pad2)") (class "Default")
      (node (ref "C81") (pin "2") (pinfunction "2_2") (pintype "passive"))
      (node (ref "R3") (pin "2") (pinfunction "2_2") (pintype "passive"))
      (node (ref "R53") (pin "1") (pinfunction "1_1") (pintype "passive"))
    )
    (net (code "26") (name "Net-(C83-Pad2)") (class "Default")
      (node (ref "C83") (pin "2") (pinfunction "2_2") (pintype "passive"))
      (node (ref "R68") (pin "2") (pinfunction "2_2") (pintype "passive"))
      (node (ref "R69") (pin "1") (pinfunction "1_1") (pintype "passive"))
    )
    (net (code "27") (name "Net-(C87-Pad2)") (class "Default")
      (node (ref "C87") (pin "2") (pinfunction "2_2") (pintype "passive"))
      (node (ref "R72") (pin "2") (pinfunction "2_2") (pintype "passive"))
      (node (ref "R73") (pin "1") (pinfunction "1_1") (pintype "passive"))
    )
    (net (code "28") (name "Net-(C89-Pad2)") (class "Default")
      (node (ref "C89") (pin "2") (pinfunction "2_2") (pintype "passive"))
      (node (ref "R74") (pin "2") (pinfunction "2_2") (pintype "passive"))
      (node (ref "R75") (pin "1") (pinfunction "1_1") (pintype "passive"))
    )
    (net (code "29") (name "Net-(C93-Pad2)") (class "Default")
      (node (ref "C93") (pin "2") (pinfunction "2_2") (pintype "passive"))
      (node (ref "R78") (pin "2") (pinfunction "2_2") (pintype "passive"))
      (node (ref "R79") (pin "1") (pinfunction "1_1") (pintype "passive"))
    )
    (net (code "30") (name "Net-(LED1-PadA)") (class "Default")
      (node (ref "LED1") (pin "A") (pinfunction "A_A") (pintype "passive"))
      (node (ref "R28") (pin "1") (pinfunction "1_1") (pintype "passive"))
    )
    (net (code "31") (name "Net-(LED3-PadA)") (class "Default")
      (node (ref "LED3") (pin "A") (pinfunction "A_A") (pintype "passive"))
      (node (ref "R27") (pin "1") (pinfunction "1_1") (pintype "passive"))
    )
    (net (code "32") (name "Net-(LP3992-BYPASS)") (class "Default")
      (node (ref "LP3992") (pin "4") (pinfunction "BYPASS_4") (pintype "passive"))
      (node (ref "U$5") (pin "P") (pinfunction "P_P") (pintype "bidirectional"))
    )
    (net (code "33") (name "Net-(U$1-1IN+)") (class "Default")
      (node (ref "R5") (pin "2") (pinfunction "2_2") (pintype "passive"))
      (node (ref "R7") (pin "2") (pinfunction "2_2") (pintype "passive"))
      (node (ref "U$1") (pin "3") (pinfunction "1IN+_3") (pintype "bidirectional"))
    )
    (net (code "34") (name "Net-(U$1-1IN-)") (class "Default")
      (node (ref "R4") (pin "2") (pinfunction "2_2") (pintype "passive"))
      (node (ref "R6") (pin "1") (pinfunction "1_1") (pintype "passive"))
      (node (ref "U$1") (pin "2") (pinfunction "1IN-_2") (pintype "bidirectional"))
    )
    (net (code "35") (name "Net-(U$1-2IN+)") (class "Default")
      (node (ref "R8") (pin "2") (pinfunction "2_2") (pintype "passive"))
      (node (ref "R9") (pin "2") (pinfunction "2_2") (pintype "passive"))
      (node (ref "U$1") (pin "5") (pinfunction "2IN+_5") (pintype "bidirectional"))
    )
    (net (code "36") (name "Net-(U$1-2IN-)") (class "Default")
      (node (ref "R10") (pin "2") (pinfunction "2_2") (pintype "passive"))
      (node (ref "R11") (pin "1") (pinfunction "1_1") (pintype "passive"))
      (node (ref "U$1") (pin "6") (pinfunction "2IN-_6") (pintype "bidirectional"))
    )
    (net (code "37") (name "Net-(U$1-4IN+)") (class "Default")
      (node (ref "R14") (pin "1") (pinfunction "1_1") (pintype "passive"))
      (node (ref "R15") (pin "1") (pinfunction "1_1") (pintype "passive"))
      (node (ref "U$1") (pin "12") (pinfunction "4IN+_12") (pintype "bidirectional"))
    )
    (net (code "38") (name "Net-(U$1-4IN-)") (class "Default")
      (node (ref "R12") (pin "2") (pinfunction "2_2") (pintype "passive"))
      (node (ref "R13") (pin "1") (pinfunction "1_1") (pintype "passive"))
      (node (ref "U$1") (pin "13") (pinfunction "4IN-_13") (pintype "bidirectional"))
    )
    (net (code "39") (name "Net-(U$2-1IN+)") (class "Default")
      (node (ref "R17") (pin "2") (pinfunction "2_2") (pintype "passive"))
      (node (ref "R19") (pin "2") (pinfunction "2_2") (pintype "passive"))
      (node (ref "U$2") (pin "3") (pinfunction "1IN+_3") (pintype "bidirectional"))
    )
    (net (code "40") (name "Net-(U$2-1IN-)") (class "Default")
      (node (ref "R16") (pin "2") (pinfunction "2_2") (pintype "passive"))
      (node (ref "R18") (pin "1") (pinfunction "1_1") (pintype "passive"))
      (node (ref "U$2") (pin "2") (pinfunction "1IN-_2") (pintype "bidirectional"))
    )
    (net (code "41") (name "Net-(U$2-2IN+)") (class "Default")
      (node (ref "R20") (pin "2") (pinfunction "2_2") (pintype "passive"))
      (node (ref "R23") (pin "2") (pinfunction "2_2") (pintype "passive"))
      (node (ref "U$2") (pin "5") (pinfunction "2IN+_5") (pintype "bidirectional"))
    )
    (net (code "42") (name "Net-(U$2-2IN-)") (class "Default")
      (node (ref "R24") (pin "2") (pinfunction "2_2") (pintype "passive"))
      (node (ref "R25") (pin "1") (pinfunction "1_1") (pintype "passive"))
      (node (ref "U$2") (pin "6") (pinfunction "2IN-_6") (pintype "bidirectional"))
    )
    (net (code "43") (name "Net-(U$2-4IN+)") (class "Default")
      (node (ref "R30") (pin "1") (pinfunction "1_1") (pintype "passive"))
      (node (ref "R31") (pin "1") (pinfunction "1_1") (pintype "passive"))
      (node (ref "U$2") (pin "12") (pinfunction "4IN+_12") (pintype "bidirectional"))
    )
    (net (code "44") (name "Net-(U$2-4IN-)") (class "Default")
      (node (ref "R26") (pin "2") (pinfunction "2_2") (pintype "passive"))
      (node (ref "R29") (pin "1") (pinfunction "1_1") (pintype "passive"))
      (node (ref "U$2") (pin "13") (pinfunction "4IN-_13") (pintype "bidirectional"))
    )
    (net (code "45") (name "VPS1_AD") (class "Default")
      (node (ref "R17") (pin "1") (pinfunction "1_1") (pintype "passive"))
      (node (ref "U$28") (pin "6") (pinfunction "OUTPUT_6") (pintype "bidirectional"))
      (node (ref "VPS_AD") (pin "1") (pinfunction "1_1") (pintype "passive"))
    )
    (net (code "46") (name "VPS1_FILTER") (class "Default")
      (node (ref "C94") (pin "1") (pinfunction "1_1") (pintype "passive"))
      (node (ref "R79") (pin "2") (pinfunction "2_2") (pintype "passive"))
      (node (ref "U$6") (pin "5") (pinfunction "2IN+_5") (pintype "bidirectional"))
    )
    (net (code "47") (name "VPS1_N") (class "Default")
      (node (ref "R49") (pin "1") (pinfunction "1_1") (pintype "passive"))
      (node (ref "R57") (pin "1") (pinfunction "1_1") (pintype "passive"))
      (node (ref "U$28") (pin "2") (pinfunction "-IN_2") (pintype "bidirectional"))
      (node (ref "VPS1") (pin "2") (pinfunction "2_2") (pintype "passive"))
      (node (ref "VPS1") (pin "3") (pinfunction "2_3") (pintype "passive"))
      (node (ref "VPS1") (pin "4") (pinfunction "2_4") (pintype "passive"))
      (node (ref "VPS1") (pin "5") (pinfunction "2_5") (pintype "passive"))
    )
    (net (code "48") (name "VPS1_OUT") (class "Default")
      (node (ref "C93") (pin "1") (pinfunction "1_1") (pintype "passive"))
      (node (ref "U$6") (pin "6") (pinfunction "2IN-_6") (pintype "bidirectional"))
      (node (ref "U$6") (pin "7") (pinfunction "2OUT_7") (pintype "bidirectional"))
      (node (ref "VPS_OUT") (pin "3") (pinfunction "3_3") (pintype "passive"))
    )
    (net (code "49") (name "VPS1_P") (class "Default")
      (node (ref "R49") (pin "2") (pinfunction "2_2") (pintype "passive"))
      (node (ref "R57") (pin "2") (pinfunction "2_2") (pintype "passive"))
      (node (ref "U$28") (pin "3") (pinfunction "+IN_3") (pintype "bidirectional"))
      (node (ref "VPS1") (pin "1") (pinfunction "1_1") (pintype "passive"))
    )
    (net (code "50") (name "VPS1_SH") (class "Default")
      (node (ref "R18") (pin "2") (pinfunction "2_2") (pintype "passive"))
      (node (ref "R78") (pin "1") (pinfunction "1_1") (pintype "passive"))
      (node (ref "U$2") (pin "1") (pinfunction "1OUT_1") (pintype "bidirectional"))
    )
    (net (code "51") (name "VPS2_AD") (class "Default")
      (node (ref "R20") (pin "1") (pinfunction "1_1") (pintype "passive"))
      (node (ref "U$29") (pin "6") (pinfunction "OUTPUT_6") (pintype "bidirectional"))
      (node (ref "VPS_AD") (pin "2") (pinfunction "2_2") (pintype "passive"))
    )
    (net (code "52") (name "VPS2_FILTER") (class "Default")
      (node (ref "C90") (pin "1") (pinfunction "1_1") (pintype "passive"))
      (node (ref "R75") (pin "2") (pinfunction "2_2") (pintype "passive"))
      (node (ref "U$6") (pin "12") (pinfunction "4IN+_12") (pintype "bidirectional"))
    )
    (net (code "53") (name "VPS2_N") (class "Default")
      (node (ref "R22") (pin "1") (pinfunction "1_1") (pintype "passive"))
      (node (ref "R56") (pin "1") (pinfunction "1_1") (pintype "passive"))
      (node (ref "U$29") (pin "2") (pinfunction "-IN_2") (pintype "bidirectional"))
      (node (ref "VPS2") (pin "2") (pinfunction "2_2") (pintype "passive"))
      (node (ref "VPS2") (pin "3") (pinfunction "2_3") (pintype "passive"))
      (node (ref "VPS2") (pin "4") (pinfunction "2_4") (pintype "passive"))
      (node (ref "VPS2") (pin "5") (pinfunction "2_5") (pintype "passive"))
    )
    (net (code "54") (name "VPS2_OUT") (class "Default")
      (node (ref "C89") (pin "1") (pinfunction "1_1") (pintype "passive"))
      (node (ref "U$6") (pin "13") (pinfunction "4IN-_13") (pintype "bidirectional"))
      (node (ref "U$6") (pin "14") (pinfunction "4OUT_14") (pintype "bidirectional"))
      (node (ref "VPS_OUT") (pin "2") (pinfunction "2_2") (pintype "passive"))
    )
    (net (code "55") (name "VPS2_P") (class "Default")
      (node (ref "R22") (pin "2") (pinfunction "2_2") (pintype "passive"))
      (node (ref "R56") (pin "2") (pinfunction "2_2") (pintype "passive"))
      (node (ref "U$29") (pin "3") (pinfunction "+IN_3") (pintype "bidirectional"))
      (node (ref "VPS2") (pin "1") (pinfunction "1_1") (pintype "passive"))
    )
    (net (code "56") (name "VPS2_SH") (class "Default")
      (node (ref "R25") (pin "2") (pinfunction "2_2") (pintype "passive"))
      (node (ref "R74") (pin "1") (pinfunction "1_1") (pintype "passive"))
      (node (ref "U$2") (pin "7") (pinfunction "2OUT_7") (pintype "bidirectional"))
    )
    (net (code "57") (name "VPS3_AD") (class "Default")
      (node (ref "R30") (pin "2") (pinfunction "2_2") (pintype "passive"))
      (node (ref "U$31") (pin "6") (pinfunction "OUTPUT_6") (pintype "bidirectional"))
      (node (ref "VPS_AD") (pin "3") (pinfunction "3_3") (pintype "passive"))
    )
    (net (code "58") (name "VPS3_FILTER") (class "Default")
      (node (ref "C82") (pin "1") (pinfunction "1_1") (pintype "passive"))
      (node (ref "R53") (pin "2") (pinfunction "2_2") (pintype "passive"))
      (node (ref "U$6") (pin "10") (pinfunction "3IN+_10") (pintype "bidirectional"))
    )
    (net (code "59") (name "VPS3_N") (class "Default")
      (node (ref "R21") (pin "1") (pinfunction "1_1") (pintype "passive"))
      (node (ref "R55") (pin "1") (pinfunction "1_1") (pintype "passive"))
      (node (ref "U$31") (pin "2") (pinfunction "-IN_2") (pintype "bidirectional"))
      (node (ref "VPS3") (pin "2") (pinfunction "2_2") (pintype "passive"))
      (node (ref "VPS3") (pin "3") (pinfunction "2_3") (pintype "passive"))
      (node (ref "VPS3") (pin "4") (pinfunction "2_4") (pintype "passive"))
      (node (ref "VPS3") (pin "5") (pinfunction "2_5") (pintype "passive"))
    )
    (net (code "60") (name "VPS3_OUT") (class "Default")
      (node (ref "C81") (pin "1") (pinfunction "1_1") (pintype "passive"))
      (node (ref "U$6") (pin "8") (pinfunction "3OUT_8") (pintype "bidirectional"))
      (node (ref "U$6") (pin "9") (pinfunction "3IN-_9") (pintype "bidirectional"))
      (node (ref "VPS_OUT") (pin "1") (pinfunction "1_1") (pintype "passive"))
    )
    (net (code "61") (name "VPS3_P") (class "Default")
      (node (ref "R21") (pin "2") (pinfunction "2_2") (pintype "passive"))
      (node (ref "R55") (pin "2") (pinfunction "2_2") (pintype "passive"))
      (node (ref "U$31") (pin "3") (pinfunction "+IN_3") (pintype "bidirectional"))
      (node (ref "VPS3") (pin "1") (pinfunction "1_1") (pintype "passive"))
    )
    (net (code "62") (name "VPS3_SH") (class "Default")
      (node (ref "R26") (pin "1") (pinfunction "1_1") (pintype "passive"))
      (node (ref "R3") (pin "1") (pinfunction "1_1") (pintype "passive"))
      (node (ref "U$2") (pin "14") (pinfunction "4OUT_14") (pintype "bidirectional"))
    )
    (net (code "63") (name "unconnected-(78L05-NC1-Pad4)") (class "Default")
      (node (ref "78L05") (pin "4") (pinfunction "NC1_4") (pintype "bidirectional"))
    )
    (net (code "64") (name "unconnected-(78L05-NC2-Pad5)") (class "Default")
      (node (ref "78L05") (pin "5") (pinfunction "NC2_5") (pintype "bidirectional"))
    )
    (net (code "65") (name "unconnected-(U$1-3IN+-Pad10)") (class "Default")
      (node (ref "U$1") (pin "10") (pinfunction "3IN+_10") (pintype "bidirectional"))
    )
    (net (code "66") (name "unconnected-(U$1-3IN--Pad9)") (class "Default")
      (node (ref "U$1") (pin "9") (pinfunction "3IN-_9") (pintype "bidirectional"))
    )
    (net (code "67") (name "unconnected-(U$1-3OUT-Pad8)") (class "Default")
      (node (ref "U$1") (pin "8") (pinfunction "3OUT_8") (pintype "bidirectional"))
    )
    (net (code "68") (name "unconnected-(U$2-3IN+-Pad10)") (class "Default")
      (node (ref "U$2") (pin "10") (pinfunction "3IN+_10") (pintype "bidirectional"))
    )
    (net (code "69") (name "unconnected-(U$2-3IN--Pad9)") (class "Default")
      (node (ref "U$2") (pin "9") (pinfunction "3IN-_9") (pintype "bidirectional"))
    )
    (net (code "70") (name "unconnected-(U$2-3OUT-Pad8)") (class "Default")
      (node (ref "U$2") (pin "8") (pinfunction "3OUT_8") (pintype "bidirectional"))
    )
    (net (code "71") (name "unconnected-(U$4-2IN+-Pad5)") (class "Default")
      (node (ref "U$4") (pin "5") (pinfunction "2IN+_5") (pintype "bidirectional"))
    )
    (net (code "72") (name "unconnected-(U$4-2IN--Pad6)") (class "Default")
      (node (ref "U$4") (pin "6") (pinfunction "2IN-_6") (pintype "bidirectional"))
    )
    (net (code "73") (name "unconnected-(U$4-2OUT-Pad7)") (class "Default")
      (node (ref "U$4") (pin "7") (pinfunction "2OUT_7") (pintype "bidirectional"))
    )
    (net (code "74") (name "unconnected-(U$6-1IN+-Pad3)") (class "Default")
      (node (ref "U$6") (pin "3") (pinfunction "1IN+_3") (pintype "bidirectional"))
    )
    (net (code "75") (name "unconnected-(U$6-1IN--Pad2)") (class "Default")
      (node (ref "U$6") (pin "2") (pinfunction "1IN-_2") (pintype "bidirectional"))
    )
    (net (code "76") (name "unconnected-(U$6-1OUT-Pad1)") (class "Default")
      (node (ref "U$6") (pin "1") (pinfunction "1OUT_1") (pintype "bidirectional"))
    )
    (net (code "77") (name "unconnected-(U$24-NC-Pad8)") (class "Default")
      (node (ref "U$24") (pin "8") (pinfunction "NC_8") (pintype "bidirectional"))
    )
    (net (code "78") (name "unconnected-(U$27-NC-Pad8)") (class "Default")
      (node (ref "U$27") (pin "8") (pinfunction "NC_8") (pintype "bidirectional"))
    )
    (net (code "79") (name "unconnected-(U$28-NC-Pad8)") (class "Default")
      (node (ref "U$28") (pin "8") (pinfunction "NC_8") (pintype "bidirectional"))
    )
    (net (code "80") (name "unconnected-(U$29-NC-Pad8)") (class "Default")
      (node (ref "U$29") (pin "8") (pinfunction "NC_8") (pintype "bidirectional"))
    )
    (net (code "81") (name "unconnected-(U$30-NC-Pad8)") (class "Default")
      (node (ref "U$30") (pin "8") (pinfunction "NC_8") (pintype "bidirectional"))
    )
    (net (code "82") (name "unconnected-(U$31-NC-Pad8)") (class "Default")
      (node (ref "U$31") (pin "8") (pinfunction "NC_8") (pintype "bidirectional"))
    )
  )
)
